# me433_PCB.net
KiCad netlist of a schematic drawn in EAGLE
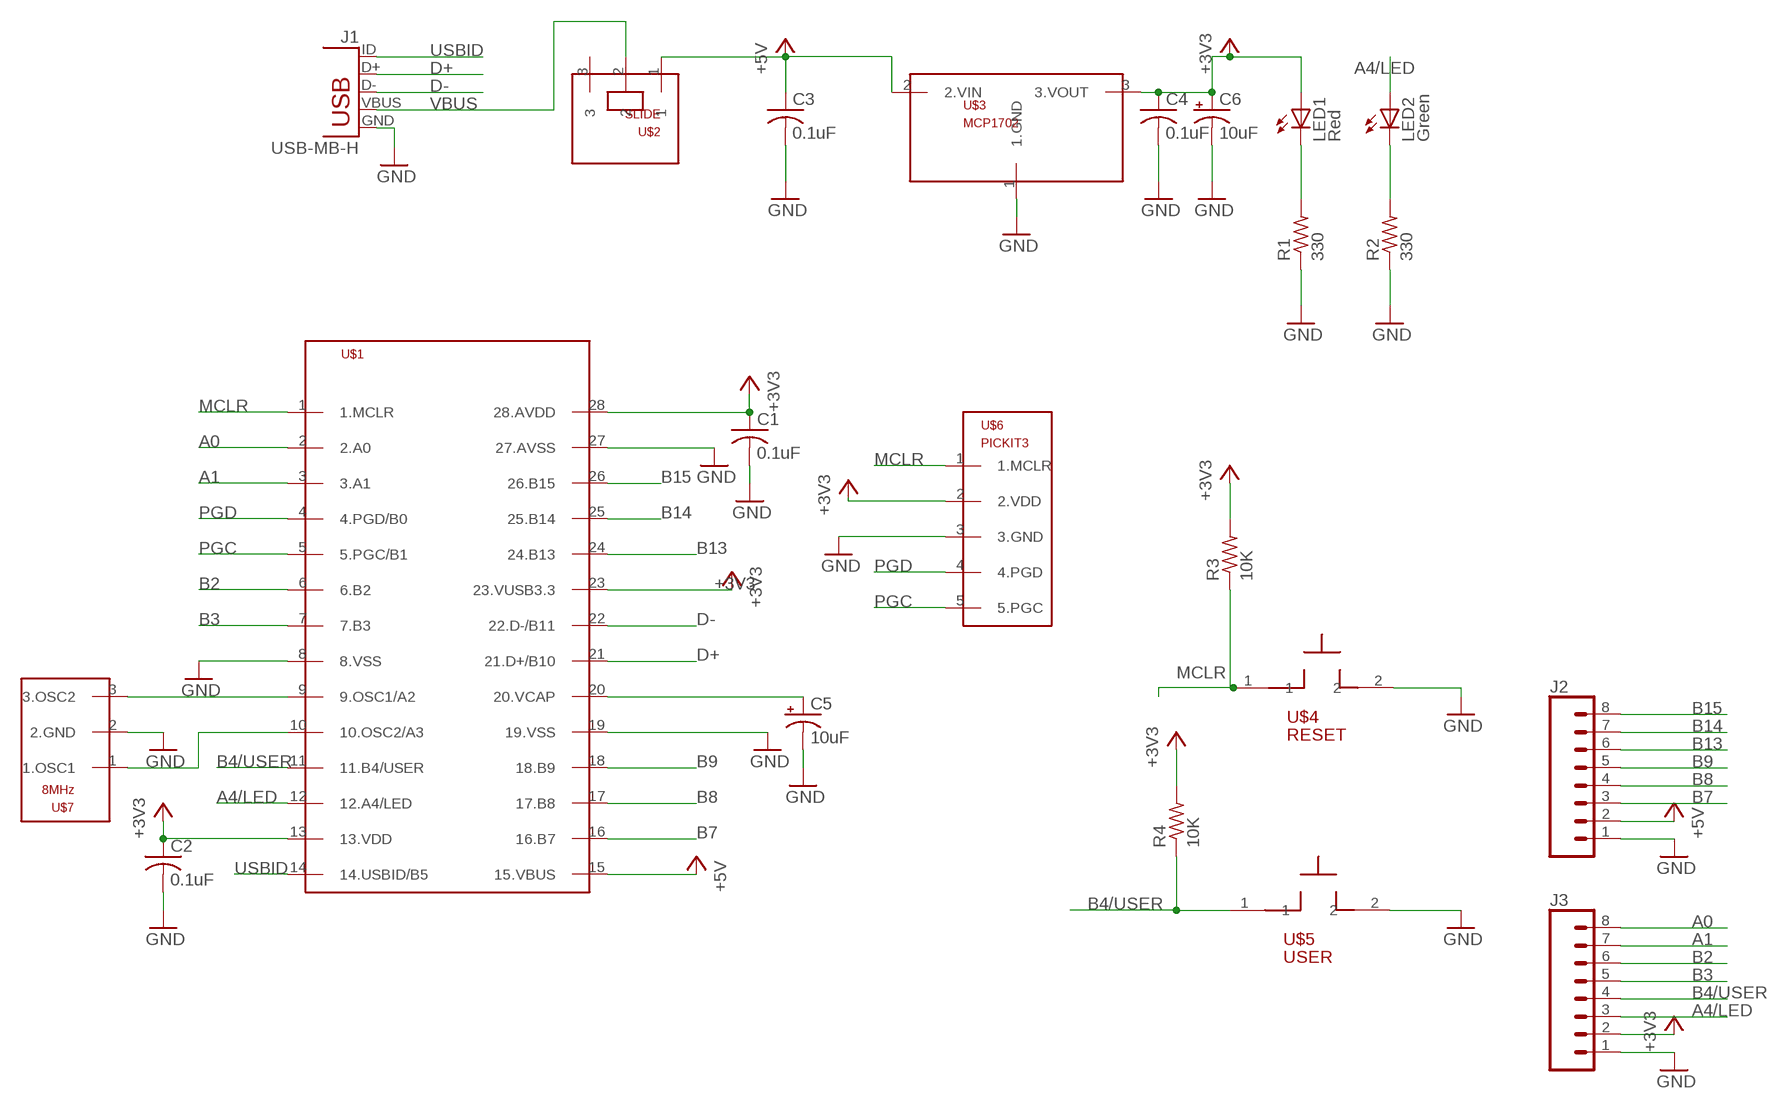
[diagram p0: schematic, sheet 1]

(export (version "E")
  (design (tool "Eeschema 10.0.6"))
  (components
    (comp (ref "C1")
      (value "0.1uF")
      (footprint "eagle-import:C025-025X050")
      (libsource (lib "eagle-import") (part "C-US025-025X050"))
    )
    (comp (ref "C2")
      (value "0.1uF")
      (footprint "eagle-import:C025-025X050")
      (libsource (lib "eagle-import") (part "C-US025-025X050"))
    )
    (comp (ref "C3")
      (value "0.1uF")
      (footprint "eagle-import:C025-025X050")
      (libsource (lib "eagle-import") (part "C-US025-025X050"))
    )
    (comp (ref "C4")
      (value "0.1uF")
      (footprint "eagle-import:C025-025X050")
      (libsource (lib "eagle-import") (part "C-US025-025X050"))
    )
    (comp (ref "C5")
      (value "10uF")
      (footprint "eagle-import:B45181B")
      (libsource (lib "eagle-import") (part "CPOL-USB45181B"))
    )
    (comp (ref "C6")
      (value "10uF")
      (footprint "eagle-import:B45181B")
      (libsource (lib "eagle-import") (part "CPOL-USB45181B"))
    )
    (comp (ref "J1")
      (value "USB-MB-H")
      (footprint "eagle-import:USB-MB-H")
      (libsource (lib "eagle-import") (part "USB-MB-H"))
    )
    (comp (ref "J2")
      (value "CONN_08\"")
      (footprint "eagle-import:1X08")
      (libsource (lib "eagle-import") (part "CONN_08{dblquote}"))
    )
    (comp (ref "J3")
      (value "CONN_08\"")
      (footprint "eagle-import:1X08")
      (libsource (lib "eagle-import") (part "CONN_08{dblquote}"))
    )
    (comp (ref "LED1")
      (value "Red")
      (footprint "eagle-import:LED3MM")
      (libsource (lib "eagle-import") (part "LED3MM"))
    )
    (comp (ref "LED2")
      (value "Green")
      (footprint "eagle-import:LED3MM")
      (libsource (lib "eagle-import") (part "LED3MM"))
    )
    (comp (ref "R1")
      (value "330")
      (footprint "eagle-import:0207_10")
      (libsource (lib "eagle-import") (part "R-US_0207/10"))
    )
    (comp (ref "R2")
      (value "330")
      (footprint "eagle-import:0207_10")
      (libsource (lib "eagle-import") (part "R-US_0207/10"))
    )
    (comp (ref "R3")
      (value "10K")
      (footprint "eagle-import:0207_10")
      (libsource (lib "eagle-import") (part "R-US_0207/10"))
    )
    (comp (ref "R4")
      (value "10K")
      (footprint "eagle-import:0207_10")
      (libsource (lib "eagle-import") (part "R-US_0207/10"))
    )
    (comp (ref "U$1")
      (value "PIC32MX250F138B")
      (footprint "eagle-import:DIL28-3")
      (libsource (lib "eagle-import") (part "PIC32MX250F138B"))
    )
    (comp (ref "U$2")
      (value "SLIDE")
      (footprint "eagle-import:SLIDE")
      (libsource (lib "eagle-import") (part "SLIDE"))
    )
    (comp (ref "U$3")
      (value "MCP1702")
      (footprint "eagle-import:TO92")
      (libsource (lib "eagle-import") (part "MCP1702"))
    )
    (comp (ref "U$4")
      (value "RESET")
      (footprint "eagle-import:PB")
      (libsource (lib "eagle-import") (part "PB"))
    )
    (comp (ref "U$5")
      (value "USER")
      (footprint "eagle-import:PB")
      (libsource (lib "eagle-import") (part "PB"))
    )
    (comp (ref "U$6")
      (value "PICKIT3")
      (footprint "eagle-import:1X05")
      (libsource (lib "eagle-import") (part "PICKIT3"))
    )
    (comp (ref "U$7")
      (value "8MHz")
      (footprint "eagle-import:OSC")
      (libsource (lib "eagle-import") (part "OSC"))
    )
  )
  (nets
    (net (code "1") (name "+3V3") (class "Default")
      (node (ref "C1") (pin "1") (pinfunction "1_1") (pintype "passive"))
      (node (ref "C2") (pin "1") (pinfunction "1_1") (pintype "passive"))
      (node (ref "C4") (pin "1") (pinfunction "1_1") (pintype "passive"))
      (node (ref "C6") (pin "+") (pinfunction "+_+") (pintype "passive"))
      (node (ref "J3") (pin "2") (pinfunction "2_2") (pintype "passive"))
      (node (ref "LED1") (pin "A") (pinfunction "A_A") (pintype "passive"))
      (node (ref "R3") (pin "2") (pinfunction "2_2") (pintype "passive"))
      (node (ref "R4") (pin "2") (pinfunction "2_2") (pintype "passive"))
      (node (ref "U$1") (pin "13") (pinfunction "13.VDD_13") (pintype "bidirectional"))
      (node (ref "U$1") (pin "23") (pinfunction "23.VUSB3.3_23") (pintype "bidirectional"))
      (node (ref "U$1") (pin "28") (pinfunction "28.AVDD_28") (pintype "bidirectional"))
      (node (ref "U$3") (pin "3") (pinfunction "3.VOUT_3") (pintype "bidirectional"))
      (node (ref "U$6") (pin "2") (pinfunction "2.VDD_2") (pintype "bidirectional"))
    )
    (net (code "2") (name "+5V") (class "Default")
      (node (ref "C3") (pin "1") (pinfunction "1_1") (pintype "passive"))
      (node (ref "J2") (pin "2") (pinfunction "2_2") (pintype "passive"))
      (node (ref "U$1") (pin "15") (pinfunction "15.VBUS_15") (pintype "bidirectional"))
      (node (ref "U$2") (pin "1") (pinfunction "1_1") (pintype "bidirectional"))
      (node (ref "U$3") (pin "2") (pinfunction "2.VIN_2") (pintype "bidirectional"))
    )
    (net (code "3") (name "/A0") (class "Default")
      (node (ref "J3") (pin "8") (pinfunction "8_8") (pintype "passive"))
      (node (ref "U$1") (pin "2") (pinfunction "2.A0_2") (pintype "bidirectional"))
    )
    (net (code "4") (name "/A1") (class "Default")
      (node (ref "J3") (pin "7") (pinfunction "7_7") (pintype "passive"))
      (node (ref "U$1") (pin "3") (pinfunction "3.A1_3") (pintype "bidirectional"))
    )
    (net (code "5") (name "/A4{slash}LED") (class "Default")
      (node (ref "J3") (pin "3") (pinfunction "3_3") (pintype "passive"))
      (node (ref "LED2") (pin "A") (pinfunction "A_A") (pintype "passive"))
      (node (ref "U$1") (pin "12") (pinfunction "12.A4/LED_12") (pintype "bidirectional"))
    )
    (net (code "6") (name "/B2") (class "Default")
      (node (ref "J3") (pin "6") (pinfunction "6_6") (pintype "passive"))
      (node (ref "U$1") (pin "6") (pinfunction "6.B2_6") (pintype "bidirectional"))
    )
    (net (code "7") (name "/B3") (class "Default")
      (node (ref "J3") (pin "5") (pinfunction "5_5") (pintype "passive"))
      (node (ref "U$1") (pin "7") (pinfunction "7.B3_7") (pintype "bidirectional"))
    )
    (net (code "8") (name "/B4{slash}USER") (class "Default")
      (node (ref "J3") (pin "4") (pinfunction "4_4") (pintype "passive"))
      (node (ref "R4") (pin "1") (pinfunction "1_1") (pintype "passive"))
      (node (ref "U$1") (pin "11") (pinfunction "11.B4/USER_11") (pintype "bidirectional"))
      (node (ref "U$5") (pin "1") (pinfunction "1_1") (pintype "bidirectional"))
    )
    (net (code "9") (name "/B7") (class "Default")
      (node (ref "J2") (pin "3") (pinfunction "3_3") (pintype "passive"))
      (node (ref "U$1") (pin "16") (pinfunction "16.B7_16") (pintype "bidirectional"))
    )
    (net (code "10") (name "/B8") (class "Default")
      (node (ref "J2") (pin "4") (pinfunction "4_4") (pintype "passive"))
      (node (ref "U$1") (pin "17") (pinfunction "17.B8_17") (pintype "bidirectional"))
    )
    (net (code "11") (name "/B9") (class "Default")
      (node (ref "J2") (pin "5") (pinfunction "5_5") (pintype "passive"))
      (node (ref "U$1") (pin "18") (pinfunction "18.B9_18") (pintype "bidirectional"))
    )
    (net (code "12") (name "/B13") (class "Default")
      (node (ref "J2") (pin "6") (pinfunction "6_6") (pintype "passive"))
      (node (ref "U$1") (pin "24") (pinfunction "24.B13_24") (pintype "bidirectional"))
    )
    (net (code "13") (name "/B14") (class "Default")
      (node (ref "J2") (pin "7") (pinfunction "7_7") (pintype "passive"))
      (node (ref "U$1") (pin "25") (pinfunction "25.B14_25") (pintype "bidirectional"))
    )
    (net (code "14") (name "/B15") (class "Default")
      (node (ref "J2") (pin "8") (pinfunction "8_8") (pintype "passive"))
      (node (ref "U$1") (pin "26") (pinfunction "26.B15_26") (pintype "bidirectional"))
    )
    (net (code "15") (name "/D+") (class "Default")
      (node (ref "J1") (pin "D+") (pinfunction "D+_D+") (pintype "bidirectional"))
      (node (ref "U$1") (pin "21") (pinfunction "21.D+/B10_21") (pintype "bidirectional"))
    )
    (net (code "16") (name "/D-") (class "Default")
      (node (ref "J1") (pin "D-") (pinfunction "D-_D-") (pintype "bidirectional"))
      (node (ref "U$1") (pin "22") (pinfunction "22.D-/B11_22") (pintype "bidirectional"))
    )
    (net (code "17") (name "/MCLR") (class "Default")
      (node (ref "R3") (pin "1") (pinfunction "1_1") (pintype "passive"))
      (node (ref "U$1") (pin "1") (pinfunction "1.MCLR_1") (pintype "bidirectional"))
      (node (ref "U$4") (pin "1") (pinfunction "1_1") (pintype "bidirectional"))
      (node (ref "U$6") (pin "1") (pinfunction "1.MCLR_1") (pintype "bidirectional"))
    )
    (net (code "18") (name "/PGC") (class "Default")
      (node (ref "U$1") (pin "5") (pinfunction "5.PGC/B1_5") (pintype "bidirectional"))
      (node (ref "U$6") (pin "5") (pinfunction "5.PGC_5") (pintype "bidirectional"))
    )
    (net (code "19") (name "/PGD") (class "Default")
      (node (ref "U$1") (pin "4") (pinfunction "4.PGD/B0_4") (pintype "bidirectional"))
      (node (ref "U$6") (pin "4") (pinfunction "4.PGD_4") (pintype "bidirectional"))
    )
    (net (code "20") (name "/USBID") (class "Default")
      (node (ref "J1") (pin "ID") (pinfunction "ID_ID") (pintype "bidirectional"))
      (node (ref "U$1") (pin "14") (pinfunction "14.USBID/B5_14") (pintype "bidirectional"))
    )
    (net (code "21") (name "/VBUS") (class "Default")
      (node (ref "J1") (pin "VBUS") (pinfunction "VBUS_VBUS") (pintype "bidirectional"))
      (node (ref "U$2") (pin "2") (pinfunction "2_2") (pintype "bidirectional"))
    )
    (net (code "22") (name "GND") (class "Default")
      (node (ref "C1") (pin "2") (pinfunction "2_2") (pintype "passive"))
      (node (ref "C2") (pin "2") (pinfunction "2_2") (pintype "passive"))
      (node (ref "C3") (pin "2") (pinfunction "2_2") (pintype "passive"))
      (node (ref "C4") (pin "2") (pinfunction "2_2") (pintype "passive"))
      (node (ref "C5") (pin "-") (pinfunction "-_-") (pintype "passive"))
      (node (ref "C6") (pin "-") (pinfunction "-_-") (pintype "passive"))
      (node (ref "J1") (pin "GND") (pinfunction "GND_GND") (pintype "bidirectional"))
      (node (ref "J2") (pin "1") (pinfunction "1_1") (pintype "passive"))
      (node (ref "J3") (pin "1") (pinfunction "1_1") (pintype "passive"))
      (node (ref "R1") (pin "1") (pinfunction "1_1") (pintype "passive"))
      (node (ref "R2") (pin "1") (pinfunction "1_1") (pintype "passive"))
      (node (ref "U$1") (pin "19") (pinfunction "19.VSS_19") (pintype "bidirectional"))
      (node (ref "U$1") (pin "27") (pinfunction "27.AVSS_27") (pintype "bidirectional"))
      (node (ref "U$1") (pin "8") (pinfunction "8.VSS_8") (pintype "bidirectional"))
      (node (ref "U$3") (pin "1") (pinfunction "1.GND_1") (pintype "bidirectional"))
      (node (ref "U$4") (pin "2") (pinfunction "2_2") (pintype "bidirectional"))
      (node (ref "U$5") (pin "2") (pinfunction "2_2") (pintype "bidirectional"))
      (node (ref "U$6") (pin "3") (pinfunction "3.GND_3") (pintype "bidirectional"))
      (node (ref "U$7") (pin "2") (pinfunction "2.GND_2") (pintype "bidirectional"))
    )
    (net (code "23") (name "Net-(LED1-C)") (class "Default")
      (node (ref "LED1") (pin "K") (pinfunction "C_K") (pintype "passive"))
      (node (ref "R1") (pin "2") (pinfunction "2_2") (pintype "passive"))
    )
    (net (code "24") (name "Net-(LED2-C)") (class "Default")
      (node (ref "LED2") (pin "K") (pinfunction "C_K") (pintype "passive"))
      (node (ref "R2") (pin "2") (pinfunction "2_2") (pintype "passive"))
    )
    (net (code "25") (name "Net-(U$1-9.OSC1{slash}A2)") (class "Default")
      (node (ref "U$1") (pin "9") (pinfunction "9.OSC1/A2_9") (pintype "bidirectional"))
      (node (ref "U$7") (pin "3") (pinfunction "3.OSC2_3") (pintype "bidirectional"))
    )
    (net (code "26") (name "Net-(U$1-10.OSC2{slash}A3)") (class "Default")
      (node (ref "U$1") (pin "10") (pinfunction "10.OSC2/A3_10") (pintype "bidirectional"))
      (node (ref "U$7") (pin "1") (pinfunction "1.OSC1_1") (pintype "bidirectional"))
    )
    (net (code "27") (name "Net-(U$1-20.VCAP)") (class "Default")
      (node (ref "C5") (pin "+") (pinfunction "+_+") (pintype "passive"))
      (node (ref "U$1") (pin "20") (pinfunction "20.VCAP_20") (pintype "bidirectional"))
    )
    (net (code "28") (name "unconnected-(U$2-Pad3)") (class "Default")
      (node (ref "U$2") (pin "3") (pinfunction "3_3") (pintype "bidirectional"))
    )
  )
)
